# brmeegpwr.net
KiCad netlist of a schematic drawn in EAGLE
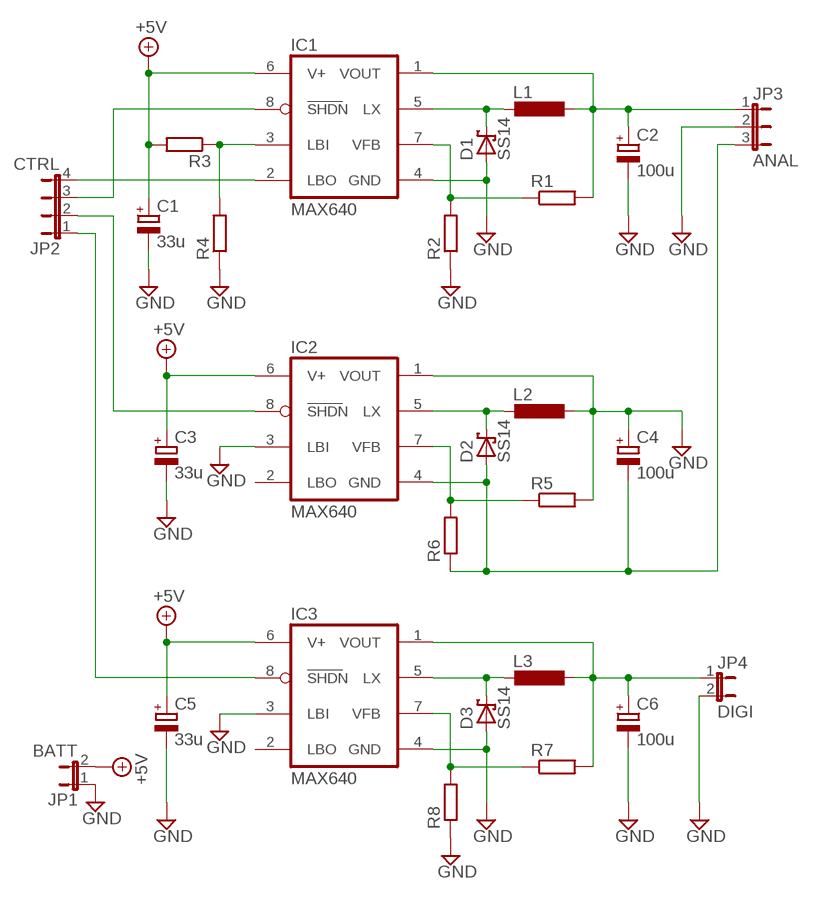
[diagram p0: schematic, sheet 1]

(export (version "E")
  (design (tool "Eeschema 10.0.6"))
  (components
    (comp (ref "C1")
      (value "33u")
      (footprint "eagle-import:SMC_C")
      (libsource (lib "eagle-import") (part "CPOL-EUSMCC"))
    )
    (comp (ref "C2")
      (value "100u")
      (footprint "eagle-import:SMC_C")
      (libsource (lib "eagle-import") (part "CPOL-EUSMCC"))
    )
    (comp (ref "C3")
      (value "33u")
      (footprint "eagle-import:SMC_C")
      (libsource (lib "eagle-import") (part "CPOL-EUSMCC"))
    )
    (comp (ref "C4")
      (value "100u")
      (footprint "eagle-import:SMC_C")
      (libsource (lib "eagle-import") (part "CPOL-EUSMCC"))
    )
    (comp (ref "C5")
      (value "33u")
      (footprint "eagle-import:SMC_C")
      (libsource (lib "eagle-import") (part "CPOL-EUSMCC"))
    )
    (comp (ref "C6")
      (value "100u")
      (footprint "eagle-import:SMC_C")
      (libsource (lib "eagle-import") (part "CPOL-EUSMCC"))
    )
    (comp (ref "D1")
      (value "SS14")
      (footprint "eagle-import:SMA")
      (libsource (lib "eagle-import") (part "SS14"))
    )
    (comp (ref "D2")
      (value "SS14")
      (footprint "eagle-import:SMA")
      (libsource (lib "eagle-import") (part "SS14"))
    )
    (comp (ref "D3")
      (value "SS14")
      (footprint "eagle-import:SMA")
      (libsource (lib "eagle-import") (part "SS14"))
    )
    (comp (ref "IC1")
      (value "MAX640")
      (footprint "eagle-import:SO08")
      (libsource (lib "eagle-import") (part "MAX640"))
    )
    (comp (ref "IC2")
      (value "MAX640")
      (footprint "eagle-import:SO08")
      (libsource (lib "eagle-import") (part "MAX640"))
    )
    (comp (ref "IC3")
      (value "MAX640")
      (footprint "eagle-import:SO08")
      (libsource (lib "eagle-import") (part "MAX640"))
    )
    (comp (ref "JP1")
      (value "BATT")
      (footprint "eagle-import:JP1")
      (libsource (lib "eagle-import") (part "JP1E"))
    )
    (comp (ref "JP2")
      (value "CTRL")
      (footprint "eagle-import:JP4")
      (libsource (lib "eagle-import") (part "JP4E"))
    )
    (comp (ref "JP3")
      (value "ANAL")
      (footprint "eagle-import:JP2")
      (libsource (lib "eagle-import") (part "JP2E"))
    )
    (comp (ref "JP4")
      (value "DIGI")
      (footprint "eagle-import:JP1")
      (libsource (lib "eagle-import") (part "JP1E"))
    )
    (comp (ref "L1")
      (value "L-EUL1812")
      (footprint "eagle-import:L1812")
      (libsource (lib "eagle-import") (part "L-EUL1812"))
    )
    (comp (ref "L2")
      (value "L-EUL1812")
      (footprint "eagle-import:L1812")
      (libsource (lib "eagle-import") (part "L-EUL1812"))
    )
    (comp (ref "L3")
      (value "L-EUL1812")
      (footprint "eagle-import:L1812")
      (libsource (lib "eagle-import") (part "L-EUL1812"))
    )
    (comp (ref "R1")
      (value "R-EU_R1206")
      (footprint "eagle-import:R1206")
      (libsource (lib "eagle-import") (part "R-EU_R1206"))
    )
    (comp (ref "R2")
      (value "R-EU_R1206")
      (footprint "eagle-import:R1206")
      (libsource (lib "eagle-import") (part "R-EU_R1206"))
    )
    (comp (ref "R3")
      (value "R-EU_R1206")
      (footprint "eagle-import:R1206")
      (libsource (lib "eagle-import") (part "R-EU_R1206"))
    )
    (comp (ref "R4")
      (value "R-EU_R1206")
      (footprint "eagle-import:R1206")
      (libsource (lib "eagle-import") (part "R-EU_R1206"))
    )
    (comp (ref "R5")
      (value "R-EU_R1206")
      (footprint "eagle-import:R1206")
      (libsource (lib "eagle-import") (part "R-EU_R1206"))
    )
    (comp (ref "R6")
      (value "R-EU_R1206")
      (footprint "eagle-import:R1206")
      (libsource (lib "eagle-import") (part "R-EU_R1206"))
    )
    (comp (ref "R7")
      (value "R-EU_R1206")
      (footprint "eagle-import:R1206")
      (libsource (lib "eagle-import") (part "R-EU_R1206"))
    )
    (comp (ref "R8")
      (value "R-EU_R1206")
      (footprint "eagle-import:R1206")
      (libsource (lib "eagle-import") (part "R-EU_R1206"))
    )
  )
  (nets
    (net (code "1") (name "+5V") (class "Default")
      (node (ref "C1") (pin "+") (pinfunction "+_+") (pintype "passive"))
      (node (ref "C3") (pin "+") (pinfunction "+_+") (pintype "passive"))
      (node (ref "C5") (pin "+") (pinfunction "+_+") (pintype "passive"))
      (node (ref "IC1") (pin "6") (pinfunction "V+_6") (pintype "power_in"))
      (node (ref "IC2") (pin "6") (pinfunction "V+_6") (pintype "power_in"))
      (node (ref "IC3") (pin "6") (pinfunction "V+_6") (pintype "power_in"))
      (node (ref "JP1") (pin "2") (pinfunction "2_2") (pintype "passive"))
      (node (ref "R3") (pin "2") (pinfunction "2_2") (pintype "passive"))
    )
    (net (code "2") (name "GND") (class "Default")
      (node (ref "C1") (pin "-") (pinfunction "-_-") (pintype "passive"))
      (node (ref "C2") (pin "-") (pinfunction "-_-") (pintype "passive"))
      (node (ref "C3") (pin "-") (pinfunction "-_-") (pintype "passive"))
      (node (ref "C4") (pin "+") (pinfunction "+_+") (pintype "passive"))
      (node (ref "C5") (pin "-") (pinfunction "-_-") (pintype "passive"))
      (node (ref "C6") (pin "-") (pinfunction "-_-") (pintype "passive"))
      (node (ref "D1") (pin "A") (pinfunction "A_A") (pintype "passive"))
      (node (ref "D3") (pin "A") (pinfunction "A_A") (pintype "passive"))
      (node (ref "IC1") (pin "4") (pinfunction "GND_4") (pintype "power_in"))
      (node (ref "IC2") (pin "1") (pinfunction "VOUT_1") (pintype "output"))
      (node (ref "IC2") (pin "3") (pinfunction "LBI_3") (pintype "input"))
      (node (ref "IC3") (pin "3") (pinfunction "LBI_3") (pintype "input"))
      (node (ref "IC3") (pin "4") (pinfunction "GND_4") (pintype "power_in"))
      (node (ref "JP1") (pin "1") (pinfunction "1_1") (pintype "passive"))
      (node (ref "JP3") (pin "2") (pinfunction "2_2") (pintype "passive"))
      (node (ref "JP4") (pin "2") (pinfunction "2_2") (pintype "passive"))
      (node (ref "L2") (pin "1") (pinfunction "1_1") (pintype "passive"))
      (node (ref "R2") (pin "1") (pinfunction "1_1") (pintype "passive"))
      (node (ref "R4") (pin "1") (pinfunction "1_1") (pintype "passive"))
      (node (ref "R5") (pin "2") (pinfunction "2_2") (pintype "passive"))
      (node (ref "R8") (pin "1") (pinfunction "1_1") (pintype "passive"))
    )
    (net (code "3") (name "Net-(IC1-LBI)") (class "Default")
      (node (ref "IC1") (pin "3") (pinfunction "LBI_3") (pintype "input"))
      (node (ref "R3") (pin "1") (pinfunction "1_1") (pintype "passive"))
      (node (ref "R4") (pin "2") (pinfunction "2_2") (pintype "passive"))
    )
    (net (code "4") (name "Net-(IC1-LBO)") (class "Default")
      (node (ref "IC1") (pin "2") (pinfunction "LBO_2") (pintype "output"))
      (node (ref "JP2") (pin "4") (pinfunction "4_4") (pintype "passive"))
    )
    (net (code "5") (name "Net-(IC1-LX)") (class "Default")
      (node (ref "D1") (pin "C") (pinfunction "C_C") (pintype "passive"))
      (node (ref "IC1") (pin "5") (pinfunction "LX_5") (pintype "output"))
      (node (ref "L1") (pin "2") (pinfunction "2_2") (pintype "passive"))
    )
    (net (code "6") (name "Net-(IC1-SHDN)") (class "Default")
      (node (ref "IC1") (pin "8") (pinfunction "SHDN_8") (pintype "input"))
      (node (ref "JP2") (pin "3") (pinfunction "3_3") (pintype "passive"))
    )
    (net (code "7") (name "Net-(IC1-VFB)") (class "Default")
      (node (ref "IC1") (pin "7") (pinfunction "VFB_7") (pintype "output"))
      (node (ref "R1") (pin "1") (pinfunction "1_1") (pintype "passive"))
      (node (ref "R2") (pin "2") (pinfunction "2_2") (pintype "passive"))
    )
    (net (code "8") (name "Net-(IC1-VOUT)") (class "Default")
      (node (ref "C2") (pin "+") (pinfunction "+_+") (pintype "passive"))
      (node (ref "IC1") (pin "1") (pinfunction "VOUT_1") (pintype "output"))
      (node (ref "JP3") (pin "1") (pinfunction "1_1") (pintype "passive"))
      (node (ref "L1") (pin "1") (pinfunction "1_1") (pintype "passive"))
      (node (ref "R1") (pin "2") (pinfunction "2_2") (pintype "passive"))
    )
    (net (code "9") (name "Net-(IC2-GND)") (class "Default")
      (node (ref "C4") (pin "-") (pinfunction "-_-") (pintype "passive"))
      (node (ref "D2") (pin "A") (pinfunction "A_A") (pintype "passive"))
      (node (ref "IC2") (pin "4") (pinfunction "GND_4") (pintype "power_in"))
      (node (ref "JP3") (pin "3") (pinfunction "3_3") (pintype "passive"))
      (node (ref "R6") (pin "1") (pinfunction "1_1") (pintype "passive"))
    )
    (net (code "10") (name "Net-(IC2-LX)") (class "Default")
      (node (ref "D2") (pin "C") (pinfunction "C_C") (pintype "passive"))
      (node (ref "IC2") (pin "5") (pinfunction "LX_5") (pintype "output"))
      (node (ref "L2") (pin "2") (pinfunction "2_2") (pintype "passive"))
    )
    (net (code "11") (name "Net-(IC2-SHDN)") (class "Default")
      (node (ref "IC2") (pin "8") (pinfunction "SHDN_8") (pintype "input"))
      (node (ref "JP2") (pin "2") (pinfunction "2_2") (pintype "passive"))
    )
    (net (code "12") (name "Net-(IC2-VFB)") (class "Default")
      (node (ref "IC2") (pin "7") (pinfunction "VFB_7") (pintype "output"))
      (node (ref "R5") (pin "1") (pinfunction "1_1") (pintype "passive"))
      (node (ref "R6") (pin "2") (pinfunction "2_2") (pintype "passive"))
    )
    (net (code "13") (name "Net-(IC3-LX)") (class "Default")
      (node (ref "D3") (pin "C") (pinfunction "C_C") (pintype "passive"))
      (node (ref "IC3") (pin "5") (pinfunction "LX_5") (pintype "output"))
      (node (ref "L3") (pin "2") (pinfunction "2_2") (pintype "passive"))
    )
    (net (code "14") (name "Net-(IC3-SHDN)") (class "Default")
      (node (ref "IC3") (pin "8") (pinfunction "SHDN_8") (pintype "input"))
      (node (ref "JP2") (pin "1") (pinfunction "1_1") (pintype "passive"))
    )
    (net (code "15") (name "Net-(IC3-VFB)") (class "Default")
      (node (ref "IC3") (pin "7") (pinfunction "VFB_7") (pintype "output"))
      (node (ref "R7") (pin "1") (pinfunction "1_1") (pintype "passive"))
      (node (ref "R8") (pin "2") (pinfunction "2_2") (pintype "passive"))
    )
    (net (code "16") (name "Net-(IC3-VOUT)") (class "Default")
      (node (ref "C6") (pin "+") (pinfunction "+_+") (pintype "passive"))
      (node (ref "IC3") (pin "1") (pinfunction "VOUT_1") (pintype "output"))
      (node (ref "JP4") (pin "1") (pinfunction "1_1") (pintype "passive"))
      (node (ref "L3") (pin "1") (pinfunction "1_1") (pintype "passive"))
      (node (ref "R7") (pin "2") (pinfunction "2_2") (pintype "passive"))
    )
    (net (code "17") (name "unconnected-(IC2-LBO-Pad2)") (class "Default")
      (node (ref "IC2") (pin "2") (pinfunction "LBO_2") (pintype "output"))
    )
    (net (code "18") (name "unconnected-(IC3-LBO-Pad2)") (class "Default")
      (node (ref "IC3") (pin "2") (pinfunction "LBO_2") (pintype "output"))
    )
  )
)
